# TM2_MAIN.net
KiCad netlist of a schematic drawn in Altium Designer
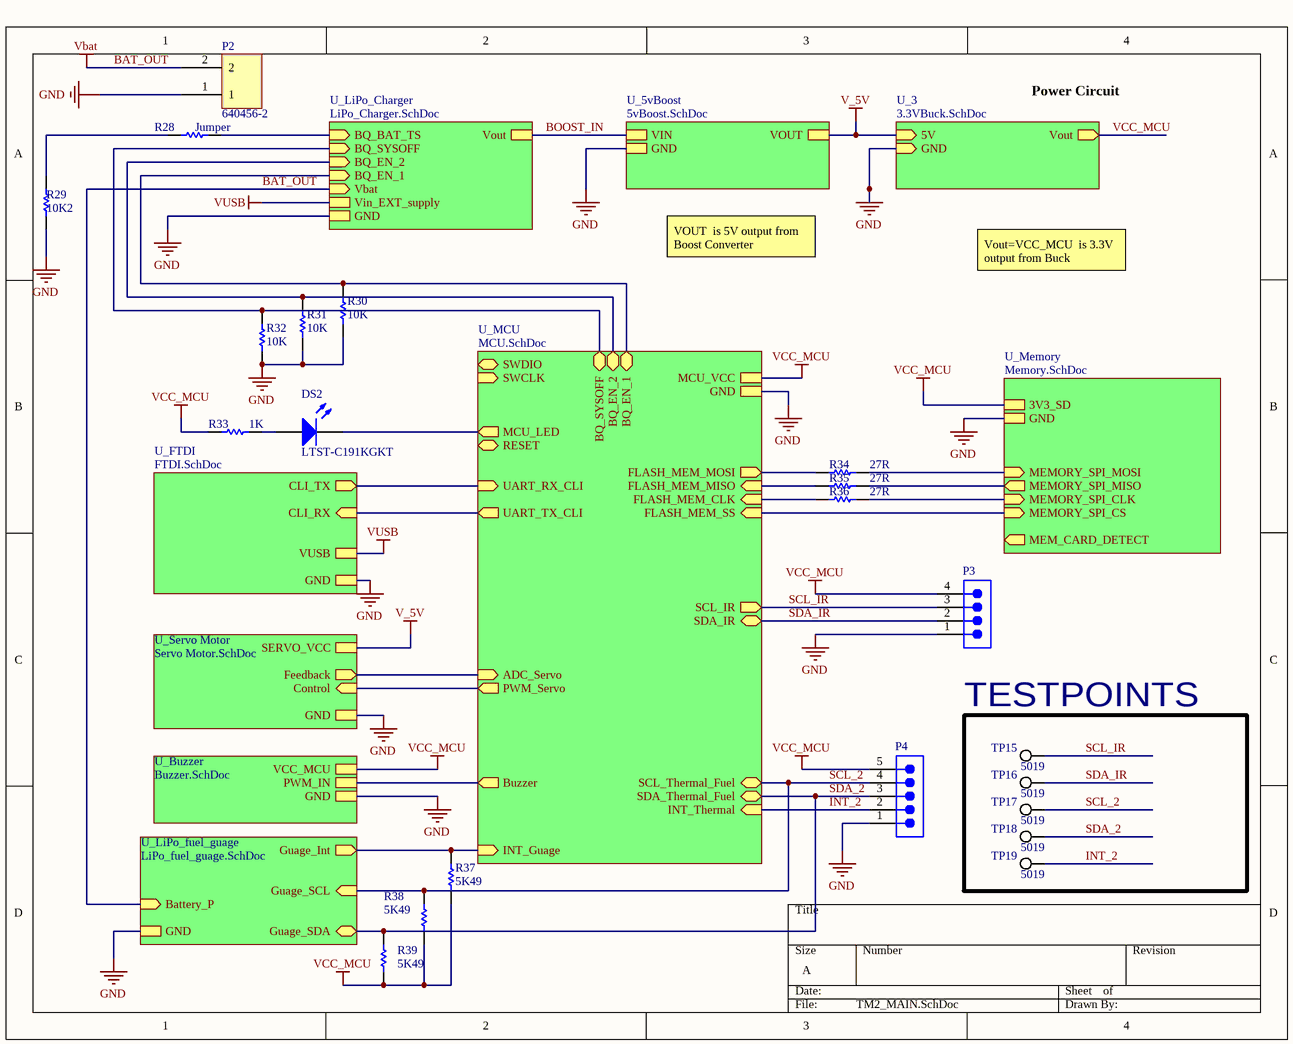
[diagram p0: TM2_MAIN.SchDoc]

(export (version "E")
  (design (tool "Eeschema 10.0.6"))
  (components
    (comp (ref "DS2")
      (value "LTST-C191KGKT")
      (footprint "LITE-ON-LTST-C191KRKT-2_V")
      (description "Chip LED, Green, 574 nm, 40 pF, -55 to 85 degC, 2-Pin SMD, RoHS, Tape and Reel")
      (fields (field (name "MANUFACTURER") "Lite-On"))
      (libsource (lib "Altium Content Vault") (part "LED-AK-2"))
    )
    (comp (ref "P2")
      (value "640456-2")
      (footprint "640456-2")
      (description "CONN HEADER VERT 2POS .100 TIN")
      (fields (field (name "MANUFACTURER") "TE Connectivity"))
      (libsource (lib "Schematics") (part "640456-2"))
    )
    (comp (ref "P3")
      (value "~")
      (footprint "SMTC-MTSW-104-07-X-S-170")
      (fields (field (name "MANUFACTURER") "Samtec") (field (name "PARTNUMBER") "MTSW-104-07-L-S-170"))
      (libsource (lib "Altium Content Vault") (part "SMTC-MTSW-104-07-X-S-170"))
    )
    (comp (ref "P4")
      (value "~")
      (footprint "SMTC-MTLW-105-05-X-S-190")
      (fields (field (name "MANUFACTURER") "Samtec") (field (name "PARTNUMBER") "MTLW-105-05-L-S-190"))
      (libsource (lib "Altium Content Vault") (part "SMTC-MTLW-105-05-X-S-190"))
    )
    (comp (ref "R28")
      (value "Jumper")
      (footprint "RESC0603(1608)_N")
      (description "Jumper 0603 (1608 Metric)")
      (fields (field (name "POWER") "None"))
      (libsource (lib "Altium Content Vault") (part "RES"))
    )
    (comp (ref "R29")
      (value "10K2")
      (footprint "RESC0805(2012)_L")
      (description "10K2 0.125W 1% 0805 (2012 Metric)  SMD")
      (fields (field (name "TOLERANCE") "1 %") (field (name "POWER") "0.125 W"))
      (libsource (lib "Altium Content Vault") (part "RES"))
    )
    (comp (ref "R30")
      (value "10K")
      (footprint "RESC0805(2012)_L")
      (description "10K2 0.125W 1% 0805 (2012 Metric)  SMD")
      (fields (field (name "TOLERANCE") "1 %") (field (name "POWER") "0.125 W"))
      (libsource (lib "Altium Content Vault") (part "RES"))
    )
    (comp (ref "R31")
      (value "10K")
      (footprint "RESC0805(2012)_L")
      (description "10K2 0.125W 1% 0805 (2012 Metric)  SMD")
      (fields (field (name "TOLERANCE") "1 %") (field (name "POWER") "0.125 W"))
      (libsource (lib "Altium Content Vault") (part "RES"))
    )
    (comp (ref "R32")
      (value "10K")
      (footprint "RESC0805(2012)_L")
      (description "10K2 0.125W 1% 0805 (2012 Metric)  SMD")
      (fields (field (name "TOLERANCE") "1 %") (field (name "POWER") "0.125 W"))
      (libsource (lib "Altium Content Vault") (part "RES"))
    )
    (comp (ref "R33")
      (value "1K")
      (footprint "RESC0603(1608)_M")
      (description "1K 0.1W 1% 0603 (1608 Metric)  SMD")
      (fields (field (name "TOLERANCE") "1 %") (field (name "POWER") "0.1 W"))
      (libsource (lib "Altium Content Vault") (part "RES"))
    )
    (comp (ref "R34")
      (value "27R")
      (footprint "RESC0603(1608)_N")
      (description "27R 0.1W 1% 0603 (1608 Metric)  SMD")
      (fields (field (name "TOLERANCE") "1 %") (field (name "POWER") "0.1 W"))
      (libsource (lib "Altium Content Vault") (part "RES"))
    )
    (comp (ref "R35")
      (value "27R")
      (footprint "RESC0603(1608)_N")
      (description "27R 0.1W 1% 0603 (1608 Metric)  SMD")
      (fields (field (name "TOLERANCE") "1 %") (field (name "POWER") "0.1 W"))
      (libsource (lib "Altium Content Vault") (part "RES"))
    )
    (comp (ref "R36")
      (value "27R")
      (footprint "RESC0603(1608)_N")
      (description "27R 0.1W 1% 0603 (1608 Metric)  SMD")
      (fields (field (name "TOLERANCE") "1 %") (field (name "POWER") "0.1 W"))
      (libsource (lib "Altium Content Vault") (part "RES"))
    )
    (comp (ref "R37")
      (value "5K49")
      (footprint "RESC0805(2012)_N")
      (description "5K49 0.125W 1% 0805 (2012 Metric)  SMD")
      (fields (field (name "TOLERANCE") "1 %") (field (name "POWER") "0.125 W"))
      (libsource (lib "Altium Content Vault") (part "RES"))
    )
    (comp (ref "R38")
      (value "5K49")
      (footprint "RESC0805(2012)_N")
      (description "5K49 0.125W 1% 0805 (2012 Metric)  SMD")
      (fields (field (name "TOLERANCE") "1 %") (field (name "POWER") "0.125 W"))
      (libsource (lib "Altium Content Vault") (part "RES"))
    )
    (comp (ref "R39")
      (value "5K49")
      (footprint "RESC0805(2012)_N")
      (description "5K49 0.125W 1% 0805 (2012 Metric)  SMD")
      (fields (field (name "TOLERANCE") "1 %") (field (name "POWER") "0.125 W"))
      (libsource (lib "Altium Content Vault") (part "RES"))
    )
    (comp (ref "TP15")
      (value "5019")
      (footprint "KSTN-5019_V")
      (description "Test Point, 1 Position SMD, RoHS, Tape and Reel")
      (libsource (lib "Altium Content Vault") (part "TESTPOINT_WHITE"))
    )
    (comp (ref "TP16")
      (value "5019")
      (footprint "KSTN-5019_V")
      (description "Test Point, 1 Position SMD, RoHS, Tape and Reel")
      (libsource (lib "Altium Content Vault") (part "TESTPOINT_WHITE"))
    )
    (comp (ref "TP17")
      (value "5019")
      (footprint "KSTN-5019_V")
      (description "Test Point, 1 Position SMD, RoHS, Tape and Reel")
      (libsource (lib "Altium Content Vault") (part "TESTPOINT_WHITE"))
    )
    (comp (ref "TP18")
      (value "5019")
      (footprint "KSTN-5019_V")
      (description "Test Point, 1 Position SMD, RoHS, Tape and Reel")
      (libsource (lib "Altium Content Vault") (part "TESTPOINT_WHITE"))
    )
    (comp (ref "TP19")
      (value "5019")
      (footprint "KSTN-5019_V")
      (description "Test Point, 1 Position SMD, RoHS, Tape and Reel")
      (libsource (lib "Altium Content Vault") (part "TESTPOINT_WHITE"))
    )
  )
  (nets
    (net (code "2") (name "/BQ_BAT_TS") (class "Default")
      (node (ref "R28") (pin "2") (pinfunction "2_2") (pintype "passive"))
    )
    (net (code "3") (name "/BQ_EN_2") (class "Default")
      (node (ref "R31") (pin "1") (pinfunction "1_1") (pintype "passive"))
    )
    (net (code "4") (name "/BQ_SYSOFF") (class "Default")
      (node (ref "R32") (pin "1") (pinfunction "1_1") (pintype "passive"))
    )
    (net (code "7") (name "/FLASH_MEM_CLK") (class "Default")
      (node (ref "R36") (pin "1") (pinfunction "1_1") (pintype "passive"))
    )
    (net (code "8") (name "/FLASH_MEM_MISO") (class "Default")
      (node (ref "R35") (pin "1") (pinfunction "1_1") (pintype "passive"))
    )
    (net (code "9") (name "/FLASH_MEM_MOSI") (class "Default")
      (node (ref "R34") (pin "1") (pinfunction "1_1") (pintype "passive"))
    )
    (net (code "12") (name "/Guage_Int") (class "Default")
      (node (ref "R37") (pin "2") (pinfunction "2_2") (pintype "passive"))
    )
    (net (code "13") (name "/INT_2") (class "Default")
      (node (ref "P4") (pin "2") (pinfunction "2_2") (pintype "passive"))
      (node (ref "TP19") (pin "1") (pinfunction "1_1") (pintype "passive"))
    )
    (net (code "14") (name "/MCU_LED") (class "Default")
      (node (ref "DS2") (pin "2") (pinfunction "K_2") (pintype "passive"))
    )
    (net (code "15") (name "/MEMORY_SPI_CLK") (class "Default")
      (node (ref "R36") (pin "2") (pinfunction "2_2") (pintype "passive"))
    )
    (net (code "16") (name "/MEMORY_SPI_MISO") (class "Default")
      (node (ref "R35") (pin "2") (pinfunction "2_2") (pintype "passive"))
    )
    (net (code "17") (name "/MEMORY_SPI_MOSI") (class "Default")
      (node (ref "R34") (pin "2") (pinfunction "2_2") (pintype "passive"))
    )
    (net (code "21") (name "/SCL_2") (class "Default")
      (node (ref "P4") (pin "4") (pinfunction "4_4") (pintype "passive"))
      (node (ref "R38") (pin "2") (pinfunction "2_2") (pintype "passive"))
      (node (ref "TP17") (pin "1") (pinfunction "1_1") (pintype "passive"))
    )
    (net (code "22") (name "/SCL_IR") (class "Default")
      (node (ref "P3") (pin "3") (pinfunction "3_3") (pintype "passive"))
      (node (ref "TP15") (pin "1") (pinfunction "1_1") (pintype "passive"))
    )
    (net (code "23") (name "/SDA_2") (class "Default")
      (node (ref "P4") (pin "3") (pinfunction "3_3") (pintype "passive"))
      (node (ref "R39") (pin "2") (pinfunction "2_2") (pintype "passive"))
      (node (ref "TP18") (pin "1") (pinfunction "1_1") (pintype "passive"))
    )
    (net (code "24") (name "/SDA_IR") (class "Default")
      (node (ref "P3") (pin "2") (pinfunction "2_2") (pintype "passive"))
      (node (ref "TP16") (pin "1") (pinfunction "1_1") (pintype "passive"))
    )
    (net (code "28") (name "GND") (class "Default")
      (node (ref "P2") (pin "1") (pinfunction "1_1") (pintype "passive"))
      (node (ref "P3") (pin "1") (pinfunction "1_1") (pintype "passive"))
      (node (ref "P4") (pin "1") (pinfunction "1_1") (pintype "passive"))
      (node (ref "R29") (pin "1") (pinfunction "1_1") (pintype "passive"))
      (node (ref "R30") (pin "1") (pinfunction "1_1") (pintype "passive"))
      (node (ref "R31") (pin "2") (pinfunction "2_2") (pintype "passive"))
      (node (ref "R32") (pin "2") (pinfunction "2_2") (pintype "passive"))
    )
    (net (code "29") (name "Net-(DS2-A)") (class "Default")
      (node (ref "DS2") (pin "1") (pinfunction "A_1") (pintype "passive"))
      (node (ref "R33") (pin "2") (pinfunction "2_2") (pintype "passive"))
    )
    (net (code "30") (name "Net-(R28-Pad1)") (class "Default")
      (node (ref "R28") (pin "1") (pinfunction "1_1") (pintype "passive"))
      (node (ref "R29") (pin "2") (pinfunction "2_2") (pintype "passive"))
    )
    (net (code "31") (name "VCC_MCU") (class "Default")
      (node (ref "P3") (pin "4") (pinfunction "4_4") (pintype "passive"))
      (node (ref "P4") (pin "5") (pinfunction "5_5") (pintype "passive"))
      (node (ref "R33") (pin "1") (pinfunction "1_1") (pintype "passive"))
      (node (ref "R37") (pin "1") (pinfunction "1_1") (pintype "passive"))
      (node (ref "R38") (pin "1") (pinfunction "1_1") (pintype "passive"))
      (node (ref "R39") (pin "1") (pinfunction "1_1") (pintype "passive"))
    )
    (net (code "32") (name "VUSB") (class "Default")
      (node (ref "R30") (pin "2") (pinfunction "2_2") (pintype "passive"))
    )
    (net (code "34") (name "Vbat") (class "Default")
      (node (ref "P2") (pin "2") (pinfunction "2_2") (pintype "passive"))
    )
  )
)
